# 80PIN_FMU3_REV_E.net
KiCad netlist of a schematic drawn in Altium Designer
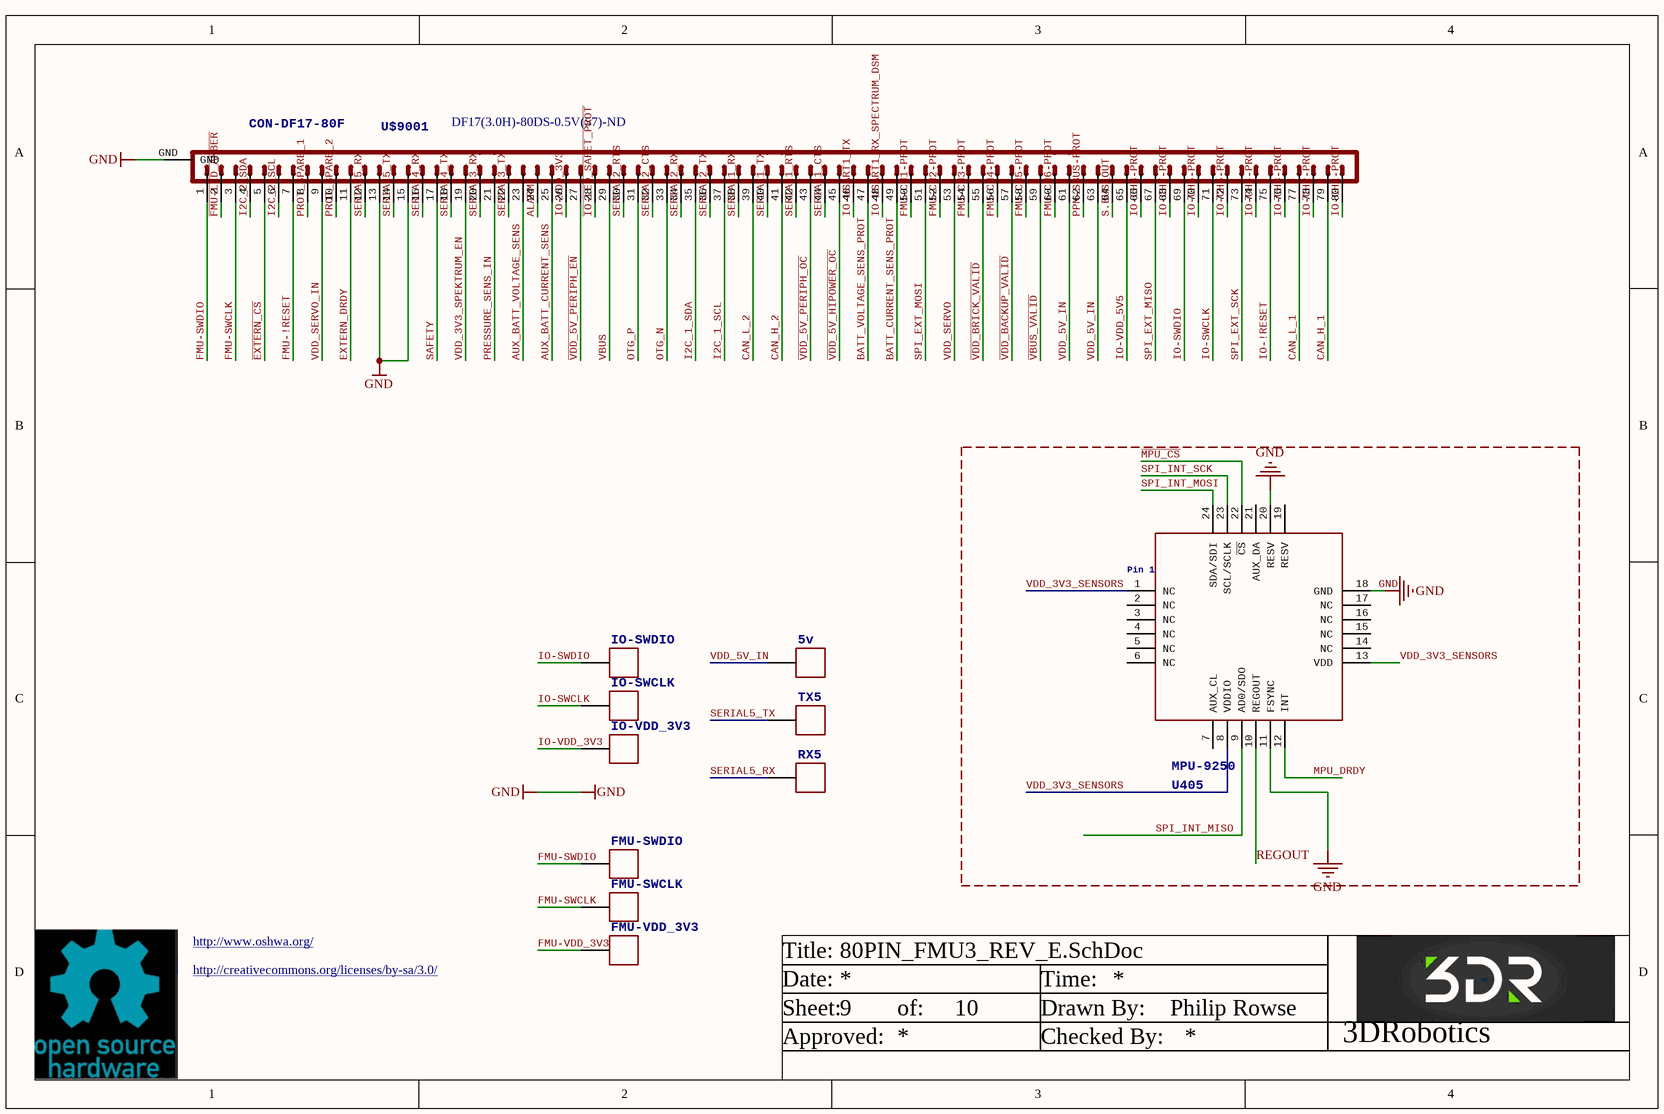
[diagram p0: 80PIN_FMU3_REV_E.SchDoc]

(export (version "E")
  (design (tool "Eeschema 10.0.6"))
  (components
    (comp (ref "5v") (value "PAD.04") (footprint "PAD.04X.04") (libsource (lib "pixhawk2") (part "PAD.04")))
    (comp (ref "FMU-SWCLK")
      (value "PAD.04")
      (footprint "PAD.04X.04")
      (libsource (lib "pixhawk2") (part "PAD.04"))
    )
    (comp (ref "FMU-SWDIO")
      (value "PAD.04")
      (footprint "PAD.04X.04")
      (libsource (lib "pixhawk2") (part "PAD.04"))
    )
    (comp (ref "FMU-VDD_3V3")
      (value "PAD.04")
      (footprint "PAD.04X.04")
      (libsource (lib "pixhawk2") (part "PAD.04"))
    )
    (comp (ref "IO-SWCLK")
      (value "PAD.04")
      (footprint "PAD.04X.04")
      (libsource (lib "pixhawk2") (part "PAD.04"))
    )
    (comp (ref "IO-SWDIO")
      (value "PAD.04")
      (footprint "PAD.04X.04")
      (libsource (lib "pixhawk2") (part "PAD.04"))
    )
    (comp (ref "IO-VDD_3V3")
      (value "PAD.04")
      (footprint "PAD.04X.04")
      (libsource (lib "pixhawk2") (part "PAD.04"))
    )
    (comp (ref "RX5") (value "PAD.04") (footprint "PAD.04X.04") (libsource (lib "pixhawk2") (part "PAD.04")))
    (comp (ref "TX5") (value "PAD.04") (footprint "PAD.04X.04") (libsource (lib "pixhawk2") (part "PAD.04")))
    (comp (ref "U$9001")
      (value "CON-DF17-80F")
      (footprint "CON-DF17-80F")
      (description "CONN RECEPT 80POS .5MM SMD W/FIT")
      (fields
        (field (name "SUPPLIER PART NUMBER 1") "DF17(3.0H)-80DS-0.5V(57)-ND")
        (field (name "3DR_PARTNO") "ECM0518")
        (field (name "PARTNO") "DF17(3.0H)-80DS-0.5V(57)")
      )
      (libsource (lib "pixhawk2") (part "CON-DF17-80F"))
    )
    (comp (ref "U405")
      (value "MPU-9250")
      (footprint "MPU-9250")
      (fields (field (name "PIN 1") "Pin 1"))
      (libsource (lib "pixhawk2") (part "MPU-6500"))
    )
  )
  (nets
    (net (code "1") (name "/ALARM") (class "Default")
      (node (ref "U$9001") (pin "24") (pinfunction "24_24") (pintype "passive"))
    )
    (net (code "2") (name "/AUX_BATT_CURRENT_SENS") (class "Default")
      (node (ref "U$9001") (pin "25") (pinfunction "25_25") (pintype "passive"))
    )
    (net (code "3") (name "/AUX_BATT_VOLTAGE_SENS") (class "Default")
      (node (ref "U$9001") (pin "23") (pinfunction "23_23") (pintype "passive"))
    )
    (net (code "4") (name "/BATT_CURRENT_SENS_PROT") (class "Default")
      (node (ref "U$9001") (pin "49") (pinfunction "49_49") (pintype "passive"))
    )
    (net (code "5") (name "/BATT_VOLTAGE_SENS_PROT") (class "Default")
      (node (ref "U$9001") (pin "47") (pinfunction "47_47") (pintype "passive"))
    )
    (net (code "6") (name "/CAN_H_1") (class "Default")
      (node (ref "U$9001") (pin "79") (pinfunction "79_79") (pintype "passive"))
    )
    (net (code "7") (name "/CAN_H_2") (class "Default")
      (node (ref "U$9001") (pin "41") (pinfunction "41_41") (pintype "passive"))
    )
    (net (code "8") (name "/CAN_L_1") (class "Default")
      (node (ref "U$9001") (pin "77") (pinfunction "77_77") (pintype "passive"))
    )
    (net (code "9") (name "/CAN_L_2") (class "Default")
      (node (ref "U$9001") (pin "39") (pinfunction "39_39") (pintype "passive"))
    )
    (net (code "10") (name "/EXTERN_DRDY") (class "Default")
      (node (ref "U$9001") (pin "11") (pinfunction "11_11") (pintype "passive"))
    )
    (net (code "11") (name "/FMU-!RESET") (class "Default")
      (node (ref "U$9001") (pin "7") (pinfunction "7_7") (pintype "passive"))
    )
    (net (code "12") (name "/FMU-CH1-PROT") (class "Default")
      (node (ref "U$9001") (pin "50") (pinfunction "50_50") (pintype "passive"))
    )
    (net (code "13") (name "/FMU-CH2-PROT") (class "Default")
      (node (ref "U$9001") (pin "52") (pinfunction "52_52") (pintype "passive"))
    )
    (net (code "14") (name "/FMU-CH3-PROT") (class "Default")
      (node (ref "U$9001") (pin "54") (pinfunction "54_54") (pintype "passive"))
    )
    (net (code "15") (name "/FMU-CH4-PROT") (class "Default")
      (node (ref "U$9001") (pin "56") (pinfunction "56_56") (pintype "passive"))
    )
    (net (code "16") (name "/FMU-CH5-PROT") (class "Default")
      (node (ref "U$9001") (pin "58") (pinfunction "58_58") (pintype "passive"))
    )
    (net (code "17") (name "/FMU-CH6-PROT") (class "Default")
      (node (ref "U$9001") (pin "60") (pinfunction "60_60") (pintype "passive"))
    )
    (net (code "18") (name "/FMU-SWCLK") (class "Default")
      (node (ref "FMU-SWCLK") (pin "P$1") (pinfunction "P$1_P$1") (pintype "passive"))
      (node (ref "U$9001") (pin "3") (pinfunction "3_3") (pintype "passive"))
    )
    (net (code "19") (name "/FMU-SWDIO") (class "Default")
      (node (ref "FMU-SWDIO") (pin "P$1") (pinfunction "P$1_P$1") (pintype "passive"))
      (node (ref "U$9001") (pin "1") (pinfunction "1_1") (pintype "passive"))
    )
    (net (code "20") (name "/FMU-VDD_3V3") (class "Default")
      (node (ref "FMU-VDD_3V3") (pin "P$1") (pinfunction "P$1_P$1") (pintype "passive"))
    )
    (net (code "21") (name "/I2C_1_SCL") (class "Default")
      (node (ref "U$9001") (pin "37") (pinfunction "37_37") (pintype "passive"))
    )
    (net (code "22") (name "/I2C_1_SDA") (class "Default")
      (node (ref "U$9001") (pin "35") (pinfunction "35_35") (pintype "passive"))
    )
    (net (code "23") (name "/I2C_2_SCL") (class "Default")
      (node (ref "U$9001") (pin "6") (pinfunction "6_6") (pintype "passive"))
    )
    (net (code "24") (name "/I2C_2_SDA") (class "Default")
      (node (ref "U$9001") (pin "4") (pinfunction "4_4") (pintype "passive"))
    )
    (net (code "25") (name "/IO-!RESET") (class "Default")
      (node (ref "U$9001") (pin "75") (pinfunction "75_75") (pintype "passive"))
    )
    (net (code "26") (name "/IO-CH1-PROT") (class "Default")
      (node (ref "U$9001") (pin "80") (pinfunction "80_80") (pintype "passive"))
    )
    (net (code "27") (name "/IO-CH2-PROT") (class "Default")
      (node (ref "U$9001") (pin "78") (pinfunction "78_78") (pintype "passive"))
    )
    (net (code "28") (name "/IO-CH3-PROT") (class "Default")
      (node (ref "U$9001") (pin "76") (pinfunction "76_76") (pintype "passive"))
    )
    (net (code "29") (name "/IO-CH4-PROT") (class "Default")
      (node (ref "U$9001") (pin "74") (pinfunction "74_74") (pintype "passive"))
    )
    (net (code "30") (name "/IO-CH5-PROT") (class "Default")
      (node (ref "U$9001") (pin "72") (pinfunction "72_72") (pintype "passive"))
    )
    (net (code "31") (name "/IO-CH6-PROT") (class "Default")
      (node (ref "U$9001") (pin "70") (pinfunction "70_70") (pintype "passive"))
    )
    (net (code "32") (name "/IO-CH7-PROT") (class "Default")
      (node (ref "U$9001") (pin "68") (pinfunction "68_68") (pintype "passive"))
    )
    (net (code "33") (name "/IO-CH8-PROT") (class "Default")
      (node (ref "U$9001") (pin "66") (pinfunction "66_66") (pintype "passive"))
    )
    (net (code "34") (name "/IO-SWCLK") (class "Default")
      (node (ref "IO-SWCLK") (pin "P$1") (pinfunction "P$1_P$1") (pintype "passive"))
      (node (ref "U$9001") (pin "71") (pinfunction "71_71") (pintype "passive"))
    )
    (net (code "35") (name "/IO-SWDIO") (class "Default")
      (node (ref "IO-SWDIO") (pin "P$1") (pinfunction "P$1_P$1") (pintype "passive"))
      (node (ref "U$9001") (pin "69") (pinfunction "69_69") (pintype "passive"))
    )
    (net (code "36") (name "/IO-USART1_RX_SPECTRUM_DSM") (class "Default")
      (node (ref "U$9001") (pin "48") (pinfunction "48_48") (pintype "passive"))
    )
    (net (code "37") (name "/IO-USART1_TX") (class "Default")
      (node (ref "U$9001") (pin "46") (pinfunction "46_46") (pintype "passive"))
    )
    (net (code "38") (name "/IO-VDD_3V3") (class "Default")
      (node (ref "IO-VDD_3V3") (pin "P$1") (pinfunction "P$1_P$1") (pintype "passive"))
      (node (ref "U$9001") (pin "26") (pinfunction "26_26") (pintype "passive"))
    )
    (net (code "39") (name "/IO-VDD_5V5") (class "Default")
      (node (ref "U$9001") (pin "65") (pinfunction "65_65") (pintype "passive"))
    )
    (net (code "40") (name "/MPU_DRDY") (class "Default")
      (node (ref "U405") (pin "12") (pinfunction "INT_12") (pintype "passive"))
    )
    (net (code "41") (name "/OTG_N") (class "Default")
      (node (ref "U$9001") (pin "33") (pinfunction "33_33") (pintype "passive"))
    )
    (net (code "42") (name "/OTG_P") (class "Default")
      (node (ref "U$9001") (pin "31") (pinfunction "31_31") (pintype "passive"))
    )
    (net (code "43") (name "/PPM-SBUS-PROT") (class "Default")
      (node (ref "U$9001") (pin "62") (pinfunction "62_62") (pintype "passive"))
    )
    (net (code "44") (name "/PRESSURE_SENS_IN") (class "Default")
      (node (ref "U$9001") (pin "21") (pinfunction "21_21") (pintype "passive"))
    )
    (net (code "45") (name "/PROT_SPARE_1") (class "Default")
      (node (ref "U$9001") (pin "8") (pinfunction "8_8") (pintype "passive"))
    )
    (net (code "46") (name "/PROT_SPARE_2") (class "Default")
      (node (ref "U$9001") (pin "10") (pinfunction "10_10") (pintype "passive"))
    )
    (net (code "47") (name "/REGOUT") (class "Default")
      (node (ref "U405") (pin "10") (pinfunction "REGOUT_10") (pintype "passive"))
    )
    (net (code "48") (name "/S.BUS_OUT") (class "Default")
      (node (ref "U$9001") (pin "64") (pinfunction "64_64") (pintype "passive"))
    )
    (net (code "49") (name "/SAFETY") (class "Default")
      (node (ref "U$9001") (pin "17") (pinfunction "17_17") (pintype "passive"))
    )
    (net (code "50") (name "/SERIAL1_CTS") (class "Default")
      (node (ref "U$9001") (pin "44") (pinfunction "44_44") (pintype "passive"))
    )
    (net (code "51") (name "/SERIAL1_RTS") (class "Default")
      (node (ref "U$9001") (pin "42") (pinfunction "42_42") (pintype "passive"))
    )
    (net (code "52") (name "/SERIAL1_RX") (class "Default")
      (node (ref "U$9001") (pin "38") (pinfunction "38_38") (pintype "passive"))
    )
    (net (code "53") (name "/SERIAL1_TX") (class "Default")
      (node (ref "U$9001") (pin "40") (pinfunction "40_40") (pintype "passive"))
    )
    (net (code "54") (name "/SERIAL2_CTS") (class "Default")
      (node (ref "U$9001") (pin "32") (pinfunction "32_32") (pintype "passive"))
    )
    (net (code "55") (name "/SERIAL2_RTS") (class "Default")
      (node (ref "U$9001") (pin "30") (pinfunction "30_30") (pintype "passive"))
    )
    (net (code "56") (name "/SERIAL2_RX") (class "Default")
      (node (ref "U$9001") (pin "34") (pinfunction "34_34") (pintype "passive"))
    )
    (net (code "57") (name "/SERIAL2_TX") (class "Default")
      (node (ref "U$9001") (pin "36") (pinfunction "36_36") (pintype "passive"))
    )
    (net (code "58") (name "/SERIAL3_RX") (class "Default")
      (node (ref "U$9001") (pin "20") (pinfunction "20_20") (pintype "passive"))
    )
    (net (code "59") (name "/SERIAL3_TX") (class "Default")
      (node (ref "U$9001") (pin "22") (pinfunction "22_22") (pintype "passive"))
    )
    (net (code "60") (name "/SERIAL4_RX") (class "Default")
      (node (ref "U$9001") (pin "16") (pinfunction "16_16") (pintype "passive"))
    )
    (net (code "61") (name "/SERIAL4_TX") (class "Default")
      (node (ref "U$9001") (pin "18") (pinfunction "18_18") (pintype "passive"))
    )
    (net (code "62") (name "/SERIAL5_RX") (class "Default")
      (node (ref "RX5") (pin "P$1") (pinfunction "P$1_P$1") (pintype "passive"))
      (node (ref "U$9001") (pin "12") (pinfunction "12_12") (pintype "passive"))
    )
    (net (code "63") (name "/SERIAL5_TX") (class "Default")
      (node (ref "TX5") (pin "P$1") (pinfunction "P$1_P$1") (pintype "passive"))
      (node (ref "U$9001") (pin "14") (pinfunction "14_14") (pintype "passive"))
    )
    (net (code "64") (name "/SPI_EXT_MISO") (class "Default")
      (node (ref "U$9001") (pin "67") (pinfunction "67_67") (pintype "passive"))
    )
    (net (code "65") (name "/SPI_EXT_MOSI") (class "Default")
      (node (ref "U$9001") (pin "51") (pinfunction "51_51") (pintype "passive"))
    )
    (net (code "66") (name "/SPI_EXT_SCK") (class "Default")
      (node (ref "U$9001") (pin "73") (pinfunction "73_73") (pintype "passive"))
    )
    (net (code "67") (name "/SPI_INT_MISO") (class "Default")
      (node (ref "U405") (pin "9") (pinfunction "AD0/SDO_9") (pintype "passive"))
    )
    (net (code "68") (name "/SPI_INT_MOSI") (class "Default")
      (node (ref "U405") (pin "24") (pinfunction "SDA/SDI_24") (pintype "passive"))
    )
    (net (code "69") (name "/SPI_INT_SCK") (class "Default")
      (node (ref "U405") (pin "23") (pinfunction "SCL/SCLK_23") (pintype "passive"))
    )
    (net (code "70") (name "/VBUS") (class "Default")
      (node (ref "U$9001") (pin "29") (pinfunction "29_29") (pintype "passive"))
    )
    (net (code "71") (name "/VDD_3V3_SENSORS") (class "Default")
      (node (ref "U405") (pin "1") (pinfunction "NC_1") (pintype "passive"))
      (node (ref "U405") (pin "13") (pinfunction "VDD_13") (pintype "passive"))
      (node (ref "U405") (pin "8") (pinfunction "VDDIO_8") (pintype "passive"))
    )
    (net (code "72") (name "/VDD_3V3_SPEKTRUM_EN") (class "Default")
      (node (ref "U$9001") (pin "19") (pinfunction "19_19") (pintype "passive"))
    )
    (net (code "73") (name "/VDD_5V_IN") (class "Default")
      (node (ref "5v") (pin "P$1") (pinfunction "P$1_P$1") (pintype "passive"))
      (node (ref "U$9001") (pin "61") (pinfunction "61_61") (pintype "passive"))
      (node (ref "U$9001") (pin "63") (pinfunction "63_63") (pintype "passive"))
    )
    (net (code "74") (name "/VDD_SERVO") (class "Default")
      (node (ref "U$9001") (pin "53") (pinfunction "53_53") (pintype "passive"))
    )
    (net (code "75") (name "/VDD_SERVO_IN") (class "Default")
      (node (ref "U$9001") (pin "9") (pinfunction "9_9") (pintype "passive"))
    )
    (net (code "76") (name "/~{EXTERN_CS}") (class "Default")
      (node (ref "U$9001") (pin "5") (pinfunction "5_5") (pintype "passive"))
    )
    (net (code "77") (name "/~{FMU-LED_AMBER}") (class "Default")
      (node (ref "U$9001") (pin "2") (pinfunction "2_2") (pintype "passive"))
    )
    (net (code "78") (name "/~{IO-LED_SAFET_PROT}") (class "Default")
      (node (ref "U$9001") (pin "28") (pinfunction "28_28") (pintype "passive"))
    )
    (net (code "79") (name "/~{MPU_CS}") (class "Default")
      (node (ref "U405") (pin "22") (pinfunction "~{CS}_22") (pintype "passive"))
    )
    (net (code "80") (name "/~{VBUS_VALID}") (class "Default")
      (node (ref "U$9001") (pin "59") (pinfunction "59_59") (pintype "passive"))
    )
    (net (code "81") (name "/~{VDD_5V_HIPOWER_OC}") (class "Default")
      (node (ref "U$9001") (pin "45") (pinfunction "45_45") (pintype "passive"))
    )
    (net (code "82") (name "/~{VDD_5V_PERIPH_EN}") (class "Default")
      (node (ref "U$9001") (pin "27") (pinfunction "27_27") (pintype "passive"))
    )
    (net (code "83") (name "/~{VDD_5V_PERIPH_OC}") (class "Default")
      (node (ref "U$9001") (pin "43") (pinfunction "43_43") (pintype "passive"))
    )
    (net (code "84") (name "/~{VDD_BACKUP_VALID}") (class "Default")
      (node (ref "U$9001") (pin "57") (pinfunction "57_57") (pintype "passive"))
    )
    (net (code "85") (name "/~{VDD_BRICK_VALID}") (class "Default")
      (node (ref "U$9001") (pin "55") (pinfunction "55_55") (pintype "passive"))
    )
    (net (code "86") (name "GND") (class "Default")
      (node (ref "U$9001") (pin "13") (pinfunction "13_13") (pintype "passive"))
      (node (ref "U$9001") (pin "15") (pinfunction "15_15") (pintype "passive"))
      (node (ref "U$9001") (pin "GND") (pinfunction "GND_GND") (pintype "passive"))
      (node (ref "U405") (pin "11") (pinfunction "FSYNC_11") (pintype "passive"))
      (node (ref "U405") (pin "18") (pinfunction "GND_18") (pintype "passive"))
      (node (ref "U405") (pin "20") (pinfunction "RESV_20") (pintype "passive"))
    )
    (net (code "87") (name "unconnected-(U405-AUX_CL-Pad7)") (class "Default")
      (node (ref "U405") (pin "7") (pinfunction "AUX_CL_7") (pintype "passive"))
    )
    (net (code "88") (name "unconnected-(U405-AUX_DA-Pad21)") (class "Default")
      (node (ref "U405") (pin "21") (pinfunction "AUX_DA_21") (pintype "passive"))
    )
    (net (code "89") (name "unconnected-(U405-NC-Pad2)") (class "Default")
      (node (ref "U405") (pin "2") (pinfunction "NC_2") (pintype "passive"))
    )
    (net (code "90") (name "unconnected-(U405-NC-Pad3)") (class "Default")
      (node (ref "U405") (pin "3") (pinfunction "NC_3") (pintype "passive"))
    )
    (net (code "91") (name "unconnected-(U405-NC-Pad4)") (class "Default")
      (node (ref "U405") (pin "4") (pinfunction "NC_4") (pintype "passive"))
    )
    (net (code "92") (name "unconnected-(U405-NC-Pad5)") (class "Default")
      (node (ref "U405") (pin "5") (pinfunction "NC_5") (pintype "passive"))
    )
    (net (code "93") (name "unconnected-(U405-NC-Pad6)") (class "Default")
      (node (ref "U405") (pin "6") (pinfunction "NC_6") (pintype "passive"))
    )
    (net (code "94") (name "unconnected-(U405-NC-Pad14)") (class "Default")
      (node (ref "U405") (pin "14") (pinfunction "NC_14") (pintype "passive"))
    )
    (net (code "95") (name "unconnected-(U405-NC-Pad15)") (class "Default")
      (node (ref "U405") (pin "15") (pinfunction "NC_15") (pintype "passive"))
    )
    (net (code "96") (name "unconnected-(U405-NC-Pad16)") (class "Default")
      (node (ref "U405") (pin "16") (pinfunction "NC_16") (pintype "passive"))
    )
    (net (code "97") (name "unconnected-(U405-NC-Pad17)") (class "Default")
      (node (ref "U405") (pin "17") (pinfunction "NC_17") (pintype "passive"))
    )
    (net (code "98") (name "unconnected-(U405-RESV-Pad19)") (class "Default")
      (node (ref "U405") (pin "19") (pinfunction "RESV_19") (pintype "passive"))
    )
  )
)
